# MCU_CAN.net
KiCad netlist of a schematic drawn in Altium Designer
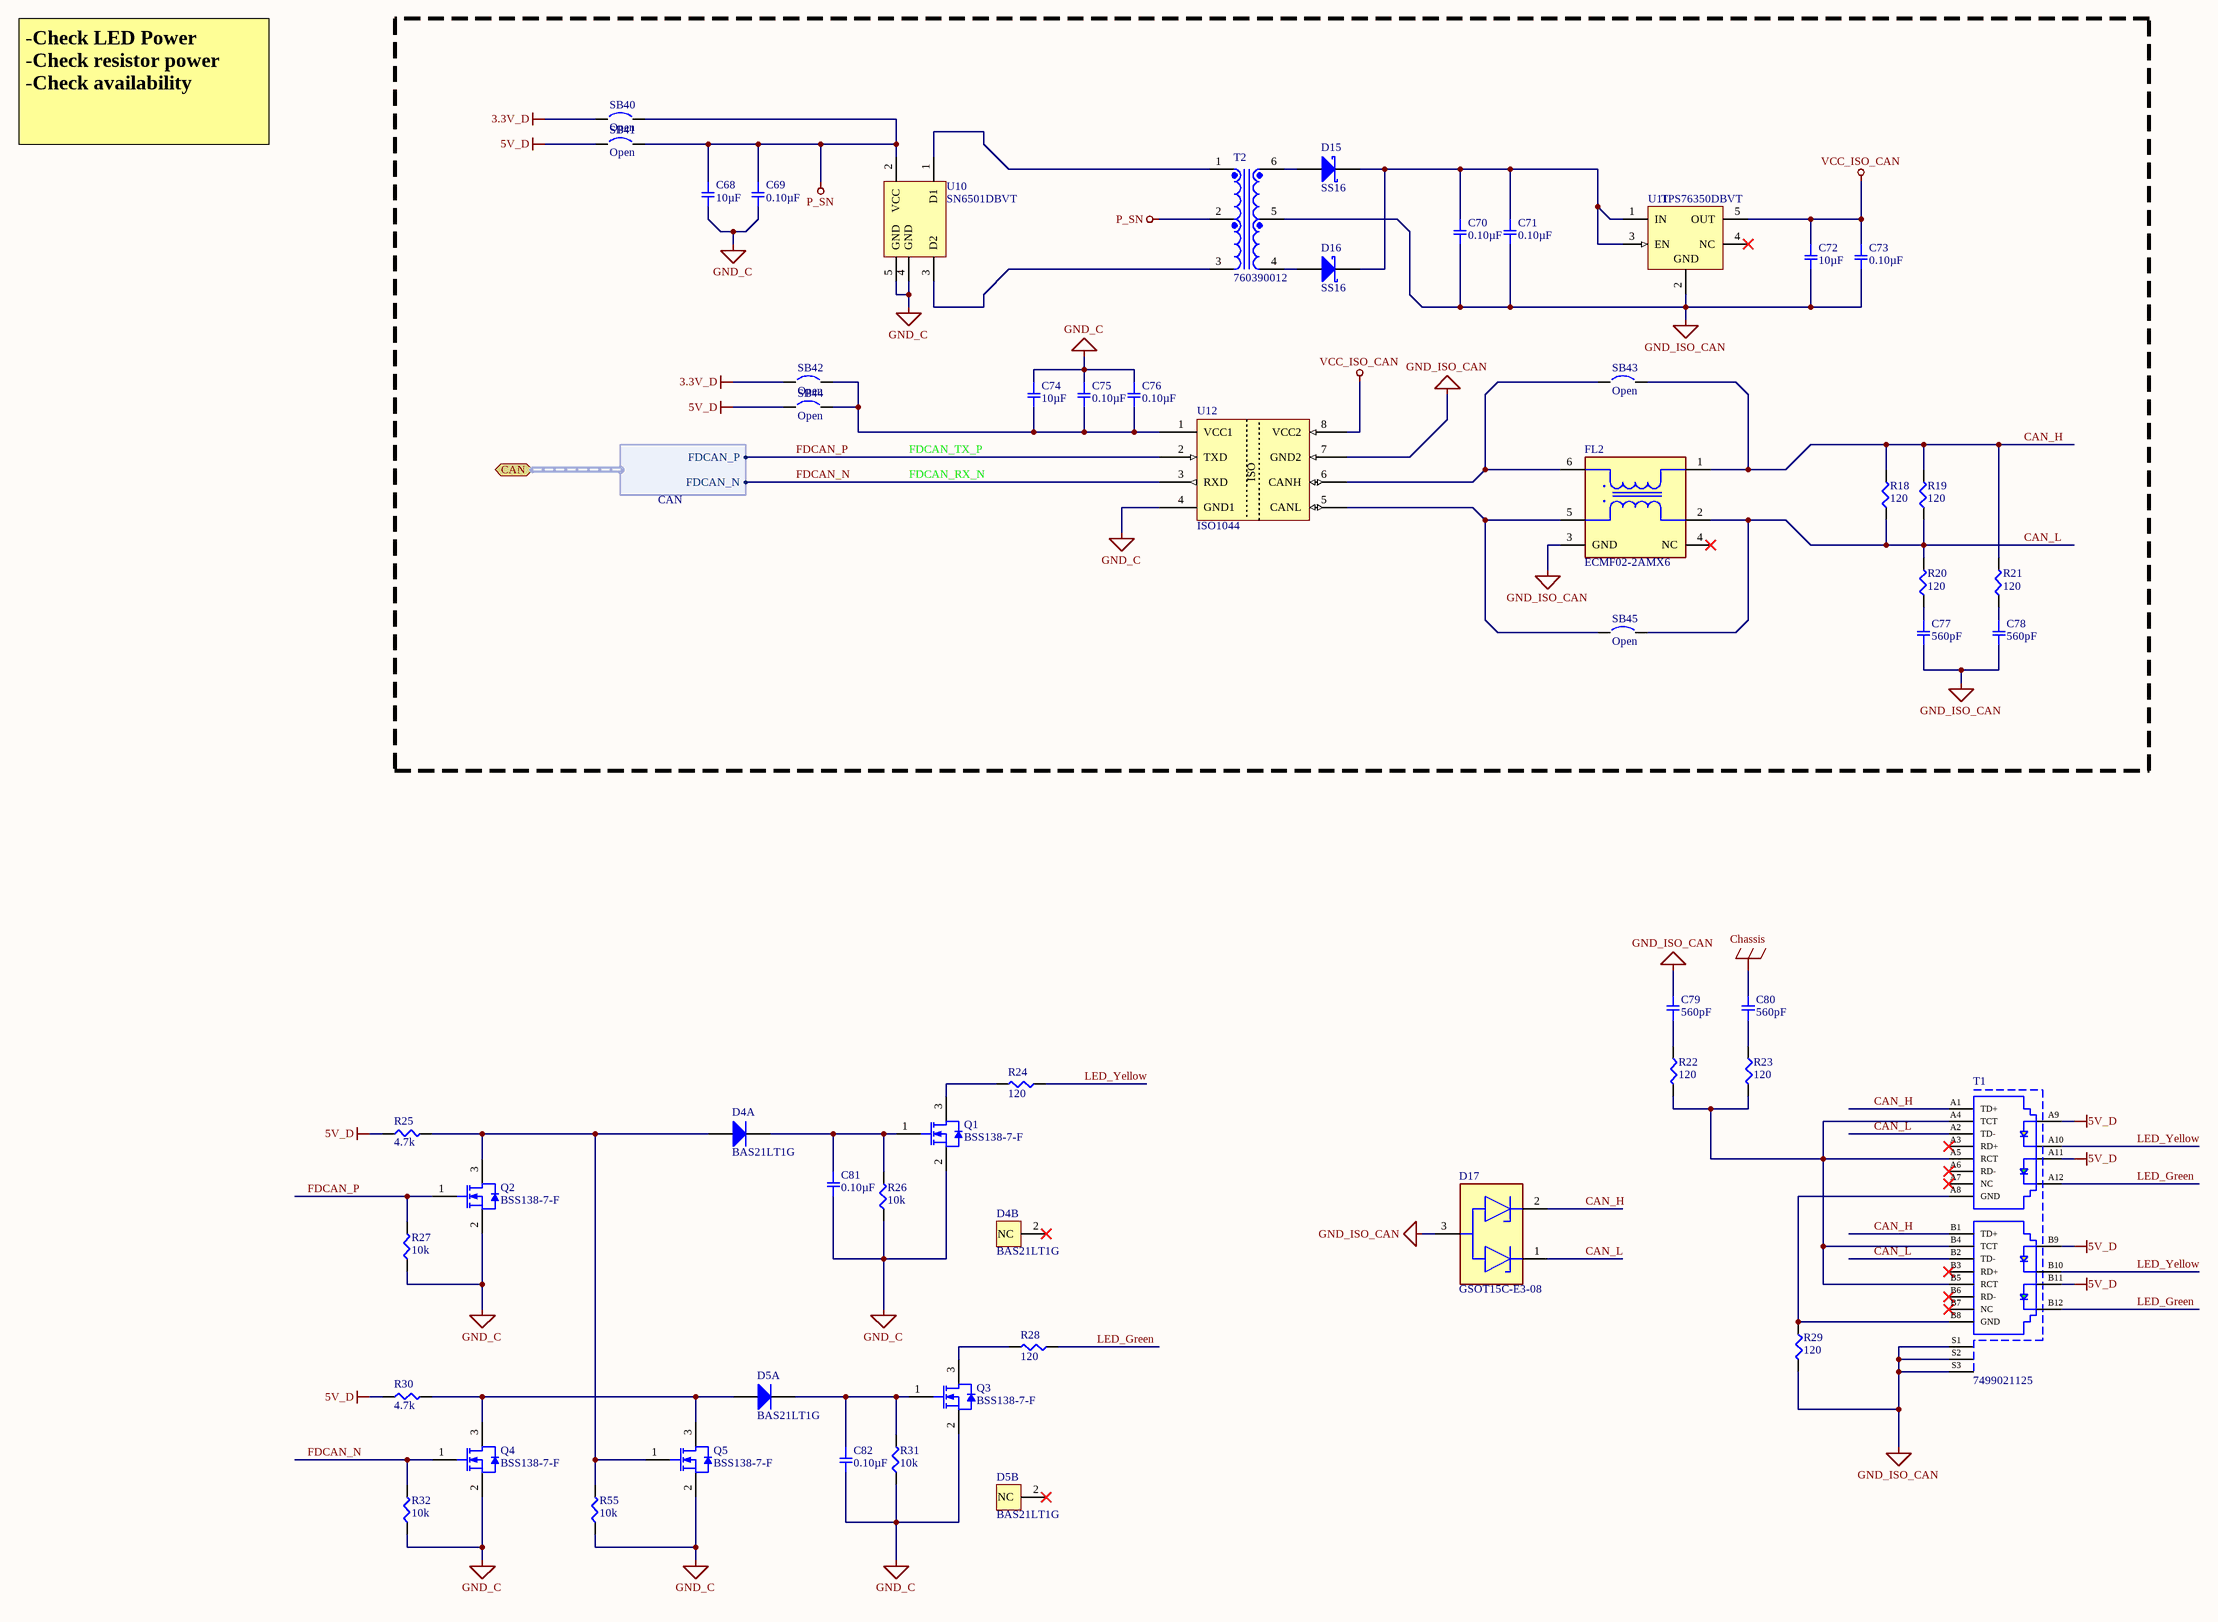
[diagram p0: MCU_CAN.SchDoc]

(export (version "E")
  (design (tool "Eeschema 10.0.6"))
  (components
    (comp (ref "C68")
      (value "10µF")
      (footprint "SMD-0805C")
      (description "CAP CER 10UF 10V X7R 0805")
      (fields
        (field (name "DIGI-KEY PART NUMBER") "490-10674-1-ND")
        (field (name "PART NUMBER") "GCM21BR71A106KE22L")
      )
      (libsource (lib "capacitor_murata_0805") (part "GCM21BR71A106KE22L"))
    )
    (comp (ref "C69")
      (value "0.10µF")
      (footprint "SMD-0805C")
      (description "CAP CER 0.1UF 100V X7R 0805")
      (fields
        (field (name "DIGI-KEY PART NUMBER") "490-5825-1-ND")
        (field (name "PART NUMBER") "GCJ21BR72A104KA01L")
      )
      (libsource (lib "capacitor_murata_0805") (part "GCJ21BR72A104KA01L"))
    )
    (comp (ref "C70")
      (value "0.10µF")
      (footprint "SMD-0805C")
      (description "CAP CER 0.1UF 100V X7R 0805")
      (fields
        (field (name "DIGI-KEY PART NUMBER") "490-5825-1-ND")
        (field (name "PART NUMBER") "GCJ21BR72A104KA01L")
      )
      (libsource (lib "capacitor_murata_0805") (part "GCJ21BR72A104KA01L"))
    )
    (comp (ref "C71")
      (value "0.10µF")
      (footprint "SMD-0805C")
      (description "CAP CER 0.1UF 100V X7R 0805")
      (fields
        (field (name "DIGI-KEY PART NUMBER") "490-5825-1-ND")
        (field (name "PART NUMBER") "GCJ21BR72A104KA01L")
      )
      (libsource (lib "capacitor_murata_0805") (part "GCJ21BR72A104KA01L"))
    )
    (comp (ref "C72")
      (value "10µF")
      (footprint "SMD-0805C")
      (description "CAP CER 10UF 10V X7R 0805")
      (fields
        (field (name "DIGI-KEY PART NUMBER") "490-10674-1-ND")
        (field (name "PART NUMBER") "GCM21BR71A106KE22L")
      )
      (libsource (lib "capacitor_murata_0805") (part "GCM21BR71A106KE22L"))
    )
    (comp (ref "C73")
      (value "0.10µF")
      (footprint "SMD-0805C")
      (description "CAP CER 0.1UF 100V X7R 0805")
      (fields
        (field (name "DIGI-KEY PART NUMBER") "490-5825-1-ND")
        (field (name "PART NUMBER") "GCJ21BR72A104KA01L")
      )
      (libsource (lib "capacitor_murata_0805") (part "GCJ21BR72A104KA01L"))
    )
    (comp (ref "C74")
      (value "10µF")
      (footprint "SMD-0805C")
      (description "CAP CER 10UF 10V X7R 0805")
      (fields
        (field (name "DIGI-KEY PART NUMBER") "490-10674-1-ND")
        (field (name "PART NUMBER") "GCM21BR71A106KE22L")
      )
      (libsource (lib "capacitor_murata_0805") (part "GCM21BR71A106KE22L"))
    )
    (comp (ref "C75")
      (value "0.10µF")
      (footprint "SMD-0805C")
      (description "CAP CER 0.1UF 100V X7R 0805")
      (fields
        (field (name "DIGI-KEY PART NUMBER") "490-5825-1-ND")
        (field (name "PART NUMBER") "GCJ21BR72A104KA01L")
      )
      (libsource (lib "capacitor_murata_0805") (part "GCJ21BR72A104KA01L"))
    )
    (comp (ref "C76")
      (value "0.10µF")
      (footprint "SMD-0805C")
      (description "CAP CER 0.1UF 100V X7R 0805")
      (fields
        (field (name "DIGI-KEY PART NUMBER") "490-5825-1-ND")
        (field (name "PART NUMBER") "GCJ21BR72A104KA01L")
      )
      (libsource (lib "capacitor_murata_0805") (part "GCJ21BR72A104KA01L"))
    )
    (comp (ref "C77")
      (value "560pF")
      (footprint "SMD-0805C")
      (description "CAP CER 560PF 50V X7R 0805")
      (fields
        (field (name "DIGI-KEY PART NUMBER") "490-11575-1-ND")
        (field (name "PART NUMBER") "GRM216R71H561KA01D")
      )
      (libsource (lib "capacitor_murata_0805") (part "GRM216R71H561KA01D"))
    )
    (comp (ref "C78")
      (value "560pF")
      (footprint "SMD-0805C")
      (description "CAP CER 560PF 50V X7R 0805")
      (fields
        (field (name "DIGI-KEY PART NUMBER") "490-11575-1-ND")
        (field (name "PART NUMBER") "GRM216R71H561KA01D")
      )
      (libsource (lib "capacitor_murata_0805") (part "GRM216R71H561KA01D"))
    )
    (comp (ref "C79")
      (value "560pF")
      (footprint "SMD-0805C")
      (description "CAP CER 560PF 50V X7R 0805")
      (fields
        (field (name "DIGI-KEY PART NUMBER") "490-11575-1-ND")
        (field (name "PART NUMBER") "GRM216R71H561KA01D")
      )
      (libsource (lib "capacitor_murata_0805") (part "GRM216R71H561KA01D"))
    )
    (comp (ref "C80")
      (value "560pF")
      (footprint "SMD-0805C")
      (description "CAP CER 560PF 50V X7R 0805")
      (fields
        (field (name "DIGI-KEY PART NUMBER") "490-11575-1-ND")
        (field (name "PART NUMBER") "GRM216R71H561KA01D")
      )
      (libsource (lib "capacitor_murata_0805") (part "GRM216R71H561KA01D"))
    )
    (comp (ref "C81")
      (value "0.10µF")
      (footprint "SMD-0805C")
      (description "CAP CER 0.1UF 100V X7R 0805")
      (fields
        (field (name "DIGI-KEY PART NUMBER") "490-5825-1-ND")
        (field (name "PART NUMBER") "GCJ21BR72A104KA01L")
      )
      (libsource (lib "capacitor_murata_0805") (part "GCJ21BR72A104KA01L"))
    )
    (comp (ref "C82")
      (value "0.10µF")
      (footprint "SMD-0805C")
      (description "CAP CER 0.1UF 100V X7R 0805")
      (fields
        (field (name "DIGI-KEY PART NUMBER") "490-5825-1-ND")
        (field (name "PART NUMBER") "GCJ21BR72A104KA01L")
      )
      (libsource (lib "capacitor_murata_0805") (part "GCJ21BR72A104KA01L"))
    )
    (comp (ref "D4")
      (value "BAS21LT1G")
      (footprint "ONSC-SOT-23-3-318-08_V")
      (description "High Voltage Switching Diode, 250 V, 3-Pin SOT-23 (318-08), Pb-Free, Tape and Reel")
      (fields (field (name "MANUFACTURER") "ON Semiconductor"))
      (libsource (lib "Altium Content Vault") (part "D-ANK-3"))
    )
    (comp (ref "D5")
      (value "BAS21LT1G")
      (footprint "ONSC-SOT-23-3-318-08_V")
      (description "High Voltage Switching Diode, 250 V, 3-Pin SOT-23 (318-08), Pb-Free, Tape and Reel")
      (fields (field (name "MANUFACTURER") "ON Semiconductor"))
      (libsource (lib "Altium Content Vault") (part "D-ANK-3"))
    )
    (comp (ref "D15")
      (value "SS16")
      (footprint "FAIR-SMA-2_B_V")
      (description "Schottky Rectifier, 700 mV, -65 to 125 degC, 2-Pin SMA, RoHS, Tape and Reel")
      (fields (field (name "MANUFACTURER") "FairchildSemiconductor"))
      (libsource (lib "Altium Content Vault") (part "DSKY-AK-2"))
    )
    (comp (ref "D16")
      (value "SS16")
      (footprint "FAIR-SMA-2_B_V")
      (description "Schottky Rectifier, 700 mV, -65 to 125 degC, 2-Pin SMA, RoHS, Tape and Reel")
      (fields (field (name "MANUFACTURER") "FairchildSemiconductor"))
      (libsource (lib "Altium Content Vault") (part "DSKY-AK-2"))
    )
    (comp (ref "D17")
      (value "GSOT15C-E3-08")
      (footprint "FP-6_541-5014_01-4-MFG")
      (description "TVS DIODE 15V 28.8V SOT23-3")
      (fields
        (field (name "MANUFACTURER") "Vishay")
        (field (name "OCTOPART") "https://octopart.com/gsot15c-e3-08-vishay-46467627")
      )
      (libsource (lib "Altium Content Vault") (part "6507c46d0de7a0efe814642e70f00b3"))
    )
    (comp (ref "FL2")
      (value "ECMF02-2AMX6")
      (footprint "FP-QFN-6L-MFG")
      (description "CMC 200MA 2LN SMD ESD")
      (fields
        (field (name "MANUFACTURER") "STMicroelectronics")
        (field (name "OCTOPART") "https://octopart.com/ecmf02-2amx6-stmicroelectronics-44353078")
      )
      (libsource (lib "Altium Content Vault") (part "8feffc7f24acfb857157da90e949b57"))
    )
    (comp (ref "Q1")
      (value "BSS138-7-F")
      (footprint "DIOD-SOT23-3_V")
      (description "N-Channel Enhancement Mode Mosfet, 50 V, 0.2 A, -55 to 150 degC, 3-Pin SOT23, RoHS, Tape and Reel")
      (fields (field (name "MANUFACTURER") "Diodes Inc"))
      (libsource (lib "Altium Content Vault") (part "NEMOS-GSD-3"))
    )
    (comp (ref "Q2")
      (value "BSS138-7-F")
      (footprint "DIOD-SOT23-3_V")
      (description "N-Channel Enhancement Mode Mosfet, 50 V, 0.2 A, -55 to 150 degC, 3-Pin SOT23, RoHS, Tape and Reel")
      (fields (field (name "MANUFACTURER") "Diodes Inc"))
      (libsource (lib "Altium Content Vault") (part "NEMOS-GSD-3"))
    )
    (comp (ref "Q3")
      (value "BSS138-7-F")
      (footprint "DIOD-SOT23-3_V")
      (description "N-Channel Enhancement Mode Mosfet, 50 V, 0.2 A, -55 to 150 degC, 3-Pin SOT23, RoHS, Tape and Reel")
      (fields (field (name "MANUFACTURER") "Diodes Inc"))
      (libsource (lib "Altium Content Vault") (part "NEMOS-GSD-3"))
    )
    (comp (ref "Q4")
      (value "BSS138-7-F")
      (footprint "DIOD-SOT23-3_V")
      (description "N-Channel Enhancement Mode Mosfet, 50 V, 0.2 A, -55 to 150 degC, 3-Pin SOT23, RoHS, Tape and Reel")
      (fields (field (name "MANUFACTURER") "Diodes Inc"))
      (libsource (lib "Altium Content Vault") (part "NEMOS-GSD-3"))
    )
    (comp (ref "Q5")
      (value "BSS138-7-F")
      (footprint "DIOD-SOT23-3_V")
      (description "N-Channel Enhancement Mode Mosfet, 50 V, 0.2 A, -55 to 150 degC, 3-Pin SOT23, RoHS, Tape and Reel")
      (fields (field (name "MANUFACTURER") "Diodes Inc"))
      (libsource (lib "Altium Content Vault") (part "NEMOS-GSD-3"))
    )
    (comp (ref "R18")
      (value "120")
      (footprint "SMD-0603-RES")
      (description "RES SMD 120 OHM 1% 1/10W 0603")
      (fields (field (name "PART NUMBER") "ERJ-3EKF1200V") (field (name "DIGI-KEY PART NUMBER") "P120HCT-ND"))
      (libsource (lib "Panasonic_ERJ_0603") (part "ERJ-3EKF1200V"))
    )
    (comp (ref "R19")
      (value "120")
      (footprint "SMD-0603-RES")
      (description "RES SMD 120 OHM 1% 1/10W 0603")
      (fields (field (name "PART NUMBER") "ERJ-3EKF1200V") (field (name "DIGI-KEY PART NUMBER") "P120HCT-ND"))
      (libsource (lib "Panasonic_ERJ_0603") (part "ERJ-3EKF1200V"))
    )
    (comp (ref "R20")
      (value "120")
      (footprint "SMD-0603-RES")
      (description "RES SMD 120 OHM 1% 1/10W 0603")
      (fields (field (name "PART NUMBER") "ERJ-3EKF1200V") (field (name "DIGI-KEY PART NUMBER") "P120HCT-ND"))
      (libsource (lib "Panasonic_ERJ_0603") (part "ERJ-3EKF1200V"))
    )
    (comp (ref "R21")
      (value "120")
      (footprint "SMD-0603-RES")
      (description "RES SMD 120 OHM 1% 1/10W 0603")
      (fields (field (name "PART NUMBER") "ERJ-3EKF1200V") (field (name "DIGI-KEY PART NUMBER") "P120HCT-ND"))
      (libsource (lib "Panasonic_ERJ_0603") (part "ERJ-3EKF1200V"))
    )
    (comp (ref "R22")
      (value "120")
      (footprint "SMD-0603-RES")
      (description "RES SMD 120 OHM 1% 1/10W 0603")
      (fields (field (name "PART NUMBER") "ERJ-3EKF1200V") (field (name "DIGI-KEY PART NUMBER") "P120HCT-ND"))
      (libsource (lib "Panasonic_ERJ_0603") (part "ERJ-3EKF1200V"))
    )
    (comp (ref "R23")
      (value "120")
      (footprint "SMD-0603-RES")
      (description "RES SMD 120 OHM 1% 1/10W 0603")
      (fields (field (name "PART NUMBER") "ERJ-3EKF1200V") (field (name "DIGI-KEY PART NUMBER") "P120HCT-ND"))
      (libsource (lib "Panasonic_ERJ_0603") (part "ERJ-3EKF1200V"))
    )
    (comp (ref "R24")
      (value "120")
      (footprint "SMD-0603-RES")
      (description "RES SMD 120 OHM 1% 1/10W 0603")
      (fields (field (name "PART NUMBER") "ERJ-3EKF1200V") (field (name "DIGI-KEY PART NUMBER") "P120HCT-ND"))
      (libsource (lib "Panasonic_ERJ_0603") (part "ERJ-3EKF1200V"))
    )
    (comp (ref "R25")
      (value "4.7k")
      (footprint "SMD-0603-RES")
      (description "RES SMD 4.7K OHM 1% 1/10W 0603")
      (fields
        (field (name "PART NUMBER") "ERJ-3EKF4701V")
        (field (name "DIGI-KEY PART NUMBER") "P4.70KHCT-ND")
      )
      (libsource (lib "Panasonic_ERJ_0603") (part "ERJ-3EKF4701V"))
    )
    (comp (ref "R26")
      (value "10k")
      (footprint "SMD-0603-RES")
      (description "RES SMD 10K OHM 1% 1/10W 0603")
      (fields
        (field (name "PART NUMBER") "ERJ-3EKF1002V")
        (field (name "DIGI-KEY PART NUMBER") "P10.0KHCT-ND")
      )
      (libsource (lib "Panasonic_ERJ_0603") (part "ERJ-3EKF1002V"))
    )
    (comp (ref "R27")
      (value "10k")
      (footprint "SMD-0603-RES")
      (description "RES SMD 10K OHM 1% 1/10W 0603")
      (fields
        (field (name "PART NUMBER") "ERJ-3EKF1002V")
        (field (name "DIGI-KEY PART NUMBER") "P10.0KHCT-ND")
      )
      (libsource (lib "Panasonic_ERJ_0603") (part "ERJ-3EKF1002V"))
    )
    (comp (ref "R28")
      (value "120")
      (footprint "SMD-0603-RES")
      (description "RES SMD 120 OHM 1% 1/10W 0603")
      (fields (field (name "PART NUMBER") "ERJ-3EKF1200V") (field (name "DIGI-KEY PART NUMBER") "P120HCT-ND"))
      (libsource (lib "Panasonic_ERJ_0603") (part "ERJ-3EKF1200V"))
    )
    (comp (ref "R29")
      (value "120")
      (footprint "SMD-0603-RES")
      (description "RES SMD 120 OHM 1% 1/10W 0603")
      (fields (field (name "PART NUMBER") "ERJ-3EKF1200V") (field (name "DIGI-KEY PART NUMBER") "P120HCT-ND"))
      (libsource (lib "Panasonic_ERJ_0603") (part "ERJ-3EKF1200V"))
    )
    (comp (ref "R30")
      (value "4.7k")
      (footprint "SMD-0603-RES")
      (description "RES SMD 4.7K OHM 1% 1/10W 0603")
      (fields
        (field (name "PART NUMBER") "ERJ-3EKF4701V")
        (field (name "DIGI-KEY PART NUMBER") "P4.70KHCT-ND")
      )
      (libsource (lib "Panasonic_ERJ_0603") (part "ERJ-3EKF4701V"))
    )
    (comp (ref "R31")
      (value "10k")
      (footprint "SMD-0603-RES")
      (description "RES SMD 10K OHM 1% 1/10W 0603")
      (fields
        (field (name "PART NUMBER") "ERJ-3EKF1002V")
        (field (name "DIGI-KEY PART NUMBER") "P10.0KHCT-ND")
      )
      (libsource (lib "Panasonic_ERJ_0603") (part "ERJ-3EKF1002V"))
    )
    (comp (ref "R32")
      (value "10k")
      (footprint "SMD-0603-RES")
      (description "RES SMD 10K OHM 1% 1/10W 0603")
      (fields
        (field (name "PART NUMBER") "ERJ-3EKF1002V")
        (field (name "DIGI-KEY PART NUMBER") "P10.0KHCT-ND")
      )
      (libsource (lib "Panasonic_ERJ_0603") (part "ERJ-3EKF1002V"))
    )
    (comp (ref "R55")
      (value "10k")
      (footprint "SMD-0603-RES")
      (description "RES SMD 10K OHM 1% 1/10W 0603")
      (fields
        (field (name "PART NUMBER") "ERJ-3EKF1002V")
        (field (name "DIGI-KEY PART NUMBER") "P10.0KHCT-ND")
      )
      (libsource (lib "Panasonic_ERJ_0603") (part "ERJ-3EKF1002V"))
    )
    (comp (ref "SB40")
      (value "Open")
      (footprint "SB_0603")
      (description "Circuit Breaker")
      (fields (field (name "PUBLISHER") "Altium Limited"))
      (libsource (lib "Edge_Card_Ucc28951") (part "Solder Bridge"))
    )
    (comp (ref "SB41")
      (value "Open")
      (footprint "SB_0603")
      (description "Circuit Breaker")
      (fields (field (name "PUBLISHER") "Altium Limited"))
      (libsource (lib "Edge_Card_Ucc28951") (part "Solder Bridge"))
    )
    (comp (ref "SB42")
      (value "Open")
      (footprint "SB_0603")
      (description "Circuit Breaker")
      (fields (field (name "PUBLISHER") "Altium Limited"))
      (libsource (lib "Edge_Card_Ucc28951") (part "Solder Bridge"))
    )
    (comp (ref "SB43")
      (value "Open")
      (footprint "SB_0603")
      (description "Circuit Breaker")
      (fields (field (name "PUBLISHER") "Altium Limited"))
      (libsource (lib "Edge_Card_Ucc28951") (part "Solder Bridge"))
    )
    (comp (ref "SB44")
      (value "Open")
      (footprint "SB_0603")
      (description "Circuit Breaker")
      (fields (field (name "PUBLISHER") "Altium Limited"))
      (libsource (lib "Edge_Card_Ucc28951") (part "Solder Bridge"))
    )
    (comp (ref "SB45")
      (value "Open")
      (footprint "SB_0603")
      (description "Circuit Breaker")
      (fields (field (name "PUBLISHER") "Altium Limited"))
      (libsource (lib "Edge_Card_Ucc28951") (part "Solder Bridge"))
    )
    (comp (ref "T1")
      (value "7499021125")
      (footprint "7499021125")
      (description "WE-RJ45 LAN Transformer, THT, 10/100 Base-T, Port 1x2, Tab Down")
      (fields (field (name "PUBLISHER") "Wurth Elektronik"))
      (libsource (lib "7499021125_Altium_WE-RJ45LAN_rev20a") (part "7499021125"))
    )
    (comp (ref "T2")
      (value "760390012")
      (footprint "WE-760390012-6_V")
      (description "Transformer, 150 mA, -40 to 125 degC, 6-Pin SMD, RoHS, Tape and Reel")
      (fields (field (name "MANUFACTURER") "Wuerth Elektronik"))
      (libsource (lib "Edge_Card_Ucc28951") (part "760039112"))
    )
    (comp (ref "U10")
      (value "SN6501DBVT")
      (footprint "SOT95P278X110-5N")
      (fields (field (name "MANUFACTURER") "TexasInstruments"))
      (libsource (lib "Edge_Card_Ucc28951") (part "SN6501"))
    )
    (comp (ref "U11")
      (value "TPS76350DBVT")
      (footprint "DBV0005A_M")
      (fields (field (name "MANUFACTURER") "Texas Instruments"))
      (libsource (lib "Altium Content Vault") (part "TI-TXX7XXXX-5"))
    )
    (comp (ref "U12")
      (value "ISO1044")
      (footprint "SOIC127P570X175_HS-9N - No Thermal")
      (description "Isolated FD CAN Transreciever")
      (libsource (lib "Edge_Card_Ucc28951") (part "ISO1044"))
    )
  )
  (nets
    (net (code "2") (name "/CAN_H") (class "Default")
      (node (ref "D17") (pin "2") (pinfunction "2_CATHODE_2") (pintype "passive"))
      (node (ref "FL2") (pin "1") (pinfunction "D+_1") (pintype "passive"))
      (node (ref "R18") (pin "2") (pinfunction "2_2") (pintype "passive"))
      (node (ref "R19") (pin "2") (pinfunction "2_2") (pintype "passive"))
      (node (ref "R21") (pin "2") (pinfunction "2_2") (pintype "passive"))
      (node (ref "SB43") (pin "2") (pinfunction "2_2") (pintype "passive"))
      (node (ref "T1") (pin "A1") (pinfunction "TD+_A1") (pintype "passive"))
      (node (ref "T1") (pin "B1") (pinfunction "TD+_B1") (pintype "passive"))
    )
    (net (code "3") (name "/CAN_L") (class "Default")
      (node (ref "D17") (pin "1") (pinfunction "1_CATHODE_1") (pintype "passive"))
      (node (ref "FL2") (pin "2") (pinfunction "D-_2") (pintype "passive"))
      (node (ref "R18") (pin "1") (pinfunction "1_1") (pintype "passive"))
      (node (ref "R19") (pin "1") (pinfunction "1_1") (pintype "passive"))
      (node (ref "R20") (pin "2") (pinfunction "2_2") (pintype "passive"))
      (node (ref "SB45") (pin "2") (pinfunction "2_2") (pintype "passive"))
      (node (ref "T1") (pin "A2") (pinfunction "TD-_A2") (pintype "passive"))
      (node (ref "T1") (pin "B2") (pinfunction "TD-_B2") (pintype "passive"))
    )
    (net (code "4") (name "/FDCAN_N") (class "Default")
      (node (ref "Q4") (pin "1") (pinfunction "G_1") (pintype "passive"))
      (node (ref "R32") (pin "2") (pinfunction "2_2") (pintype "passive"))
      (node (ref "U12") (pin "3") (pinfunction "RXD_3") (pintype "output"))
    )
    (net (code "5") (name "/FDCAN_P") (class "Default")
      (node (ref "Q2") (pin "1") (pinfunction "G_1") (pintype "passive"))
      (node (ref "R27") (pin "2") (pinfunction "2_2") (pintype "passive"))
      (node (ref "U12") (pin "2") (pinfunction "TXD_2") (pintype "input"))
    )
    (net (code "6") (name "/LED_Green") (class "Default")
      (node (ref "R28") (pin "1") (pinfunction "1_1") (pintype "passive"))
      (node (ref "T1") (pin "A12") (pinfunction "A12_A12") (pintype "passive"))
      (node (ref "T1") (pin "B12") (pinfunction "B12_B12") (pintype "passive"))
    )
    (net (code "7") (name "/LED_Yellow") (class "Default")
      (node (ref "R24") (pin "1") (pinfunction "1_1") (pintype "passive"))
      (node (ref "T1") (pin "A10") (pinfunction "A10_A10") (pintype "passive"))
      (node (ref "T1") (pin "B10") (pinfunction "B10_B10") (pintype "passive"))
    )
    (net (code "9") (name "3.3V_D") (class "Default")
      (node (ref "SB40") (pin "1") (pinfunction "1_1") (pintype "passive"))
      (node (ref "SB42") (pin "1") (pinfunction "1_1") (pintype "passive"))
    )
    (net (code "10") (name "5V_D") (class "Default")
      (node (ref "R25") (pin "1") (pinfunction "1_1") (pintype "passive"))
      (node (ref "R30") (pin "1") (pinfunction "1_1") (pintype "passive"))
      (node (ref "SB41") (pin "1") (pinfunction "1_1") (pintype "passive"))
      (node (ref "SB44") (pin "1") (pinfunction "1_1") (pintype "passive"))
      (node (ref "T1") (pin "A11") (pinfunction "A11_A11") (pintype "passive"))
      (node (ref "T1") (pin "A9") (pinfunction "A9_A9") (pintype "passive"))
      (node (ref "T1") (pin "B11") (pinfunction "B11_B11") (pintype "passive"))
      (node (ref "T1") (pin "B9") (pinfunction "B9_B9") (pintype "passive"))
    )
    (net (code "11") (name "Chassis") (class "Default")
      (node (ref "C80") (pin "2") (pinfunction "2_2") (pintype "passive"))
    )
    (net (code "12") (name "GND_C") (class "Default")
      (node (ref "C68") (pin "2") (pinfunction "2_2") (pintype "passive"))
      (node (ref "C69") (pin "2") (pinfunction "2_2") (pintype "passive"))
      (node (ref "C74") (pin "1") (pinfunction "1_1") (pintype "passive"))
      (node (ref "C75") (pin "1") (pinfunction "1_1") (pintype "passive"))
      (node (ref "C76") (pin "1") (pinfunction "1_1") (pintype "passive"))
      (node (ref "C81") (pin "2") (pinfunction "2_2") (pintype "passive"))
      (node (ref "C82") (pin "2") (pinfunction "2_2") (pintype "passive"))
      (node (ref "Q1") (pin "2") (pinfunction "S_2") (pintype "passive"))
      (node (ref "Q2") (pin "2") (pinfunction "S_2") (pintype "passive"))
      (node (ref "Q3") (pin "2") (pinfunction "S_2") (pintype "passive"))
      (node (ref "Q4") (pin "2") (pinfunction "S_2") (pintype "passive"))
      (node (ref "Q5") (pin "2") (pinfunction "S_2") (pintype "passive"))
      (node (ref "R26") (pin "1") (pinfunction "1_1") (pintype "passive"))
      (node (ref "R27") (pin "1") (pinfunction "1_1") (pintype "passive"))
      (node (ref "R31") (pin "1") (pinfunction "1_1") (pintype "passive"))
      (node (ref "R32") (pin "1") (pinfunction "1_1") (pintype "passive"))
      (node (ref "R55") (pin "1") (pinfunction "1_1") (pintype "passive"))
      (node (ref "U10") (pin "4") (pinfunction "GND_4") (pintype "power_in"))
      (node (ref "U10") (pin "5") (pinfunction "GND_5") (pintype "power_in"))
      (node (ref "U12") (pin "4") (pinfunction "GND1_4") (pintype "power_in"))
    )
    (net (code "13") (name "GND_ISO_CAN") (class "Default")
      (node (ref "C70") (pin "2") (pinfunction "2_2") (pintype "passive"))
      (node (ref "C71") (pin "2") (pinfunction "2_2") (pintype "passive"))
      (node (ref "C72") (pin "2") (pinfunction "2_2") (pintype "passive"))
      (node (ref "C73") (pin "2") (pinfunction "2_2") (pintype "passive"))
      (node (ref "C77") (pin "2") (pinfunction "2_2") (pintype "passive"))
      (node (ref "C78") (pin "2") (pinfunction "2_2") (pintype "passive"))
      (node (ref "C79") (pin "2") (pinfunction "2_2") (pintype "passive"))
      (node (ref "D17") (pin "3") (pinfunction "COMMON_ANODE_3") (pintype "passive"))
      (node (ref "FL2") (pin "3") (pinfunction "GND_3") (pintype "power_in"))
      (node (ref "R29") (pin "2") (pinfunction "2_2") (pintype "passive"))
      (node (ref "T1") (pin "S1") (pinfunction "Shield_S1") (pintype "passive"))
      (node (ref "T1") (pin "S2") (pinfunction "Shield_S2") (pintype "passive"))
      (node (ref "T1") (pin "S3") (pinfunction "Shield_S3") (pintype "passive"))
      (node (ref "T2") (pin "5") (pinfunction "5_5") (pintype "passive"))
      (node (ref "U11") (pin "2") (pinfunction "GND_2") (pintype "power_in"))
      (node (ref "U12") (pin "7") (pinfunction "GND2_7") (pintype "input"))
    )
    (net (code "14") (name "Net-(C77-Pad1)") (class "Default")
      (node (ref "C77") (pin "1") (pinfunction "1_1") (pintype "passive"))
      (node (ref "R20") (pin "1") (pinfunction "1_1") (pintype "passive"))
    )
    (net (code "15") (name "Net-(C78-Pad1)") (class "Default")
      (node (ref "C78") (pin "1") (pinfunction "1_1") (pintype "passive"))
      (node (ref "R21") (pin "1") (pinfunction "1_1") (pintype "passive"))
    )
    (net (code "16") (name "Net-(C79-Pad1)") (class "Default")
      (node (ref "C79") (pin "1") (pinfunction "1_1") (pintype "passive"))
      (node (ref "R22") (pin "1") (pinfunction "1_1") (pintype "passive"))
    )
    (net (code "17") (name "Net-(C80-Pad1)") (class "Default")
      (node (ref "C80") (pin "1") (pinfunction "1_1") (pintype "passive"))
      (node (ref "R23") (pin "1") (pinfunction "1_1") (pintype "passive"))
    )
    (net (code "18") (name "Net-(D4A-A)") (class "Default")
      (node (ref "D4") (pin "1") (pinfunction "A_1") (pintype "passive"))
      (node (ref "Q2") (pin "3") (pinfunction "D_3") (pintype "passive"))
      (node (ref "Q5") (pin "1") (pinfunction "G_1") (pintype "passive"))
      (node (ref "R25") (pin "2") (pinfunction "2_2") (pintype "passive"))
      (node (ref "R55") (pin "2") (pinfunction "2_2") (pintype "passive"))
    )
    (net (code "19") (name "Net-(D4A-K)") (class "Default")
      (node (ref "C81") (pin "1") (pinfunction "1_1") (pintype "passive"))
      (node (ref "D4") (pin "3") (pinfunction "K_3") (pintype "passive"))
      (node (ref "Q1") (pin "1") (pinfunction "G_1") (pintype "passive"))
      (node (ref "R26") (pin "2") (pinfunction "2_2") (pintype "passive"))
    )
    (net (code "20") (name "Net-(D5A-A)") (class "Default")
      (node (ref "D5") (pin "1") (pinfunction "A_1") (pintype "passive"))
      (node (ref "Q4") (pin "3") (pinfunction "D_3") (pintype "passive"))
      (node (ref "Q5") (pin "3") (pinfunction "D_3") (pintype "passive"))
      (node (ref "R30") (pin "2") (pinfunction "2_2") (pintype "passive"))
    )
    (net (code "21") (name "Net-(D5A-K)") (class "Default")
      (node (ref "C82") (pin "1") (pinfunction "1_1") (pintype "passive"))
      (node (ref "D5") (pin "3") (pinfunction "K_3") (pintype "passive"))
      (node (ref "Q3") (pin "1") (pinfunction "G_1") (pintype "passive"))
      (node (ref "R31") (pin "2") (pinfunction "2_2") (pintype "passive"))
    )
    (net (code "22") (name "Net-(D15-A)") (class "Default")
      (node (ref "D15") (pin "1") (pinfunction "A_1") (pintype "passive"))
      (node (ref "T2") (pin "6") (pinfunction "6_6") (pintype "passive"))
    )
    (net (code "23") (name "Net-(D15-K)") (class "Default")
      (node (ref "C70") (pin "1") (pinfunction "1_1") (pintype "passive"))
      (node (ref "C71") (pin "1") (pinfunction "1_1") (pintype "passive"))
      (node (ref "D15") (pin "2") (pinfunction "K_2") (pintype "passive"))
      (node (ref "D16") (pin "2") (pinfunction "K_2") (pintype "passive"))
      (node (ref "U11") (pin "1") (pinfunction "IN_1") (pintype "power_in"))
      (node (ref "U11") (pin "3") (pinfunction "EN_3") (pintype "input"))
    )
    (net (code "24") (name "Net-(D16-A)") (class "Default")
      (node (ref "D16") (pin "1") (pinfunction "A_1") (pintype "passive"))
      (node (ref "T2") (pin "4") (pinfunction "4_4") (pintype "passive"))
    )
    (net (code "25") (name "Net-(Q1-D)") (class "Default")
      (node (ref "Q1") (pin "3") (pinfunction "D_3") (pintype "passive"))
      (node (ref "R24") (pin "2") (pinfunction "2_2") (pintype "passive"))
    )
    (net (code "26") (name "Net-(Q3-D)") (class "Default")
      (node (ref "Q3") (pin "3") (pinfunction "D_3") (pintype "passive"))
      (node (ref "R28") (pin "2") (pinfunction "2_2") (pintype "passive"))
    )
    (net (code "27") (name "Net-(R22-Pad2)") (class "Default")
      (node (ref "R22") (pin "2") (pinfunction "2_2") (pintype "passive"))
      (node (ref "R23") (pin "2") (pinfunction "2_2") (pintype "passive"))
      (node (ref "T1") (pin "A4") (pinfunction "TCT_A4") (pintype "passive"))
      (node (ref "T1") (pin "A5") (pinfunction "RCT_A5") (pintype "passive"))
      (node (ref "T1") (pin "B4") (pinfunction "TCT_B4") (pintype "passive"))
      (node (ref "T1") (pin "B5") (pinfunction "RCT_B5") (pintype "passive"))
    )
    (net (code "28") (name "Net-(R29-Pad1)") (class "Default")
      (node (ref "R29") (pin "1") (pinfunction "1_1") (pintype "passive"))
      (node (ref "T1") (pin "A8") (pinfunction "GND_A8") (pintype "passive"))
      (node (ref "T1") (pin "B8") (pinfunction "GND_B8") (pintype "passive"))
    )
    (net (code "29") (name "Net-(U10-D1)") (class "Default")
      (node (ref "T2") (pin "1") (pinfunction "1_1") (pintype "passive"))
      (node (ref "U10") (pin "1") (pinfunction "D1_1") (pintype "open_collector"))
    )
    (net (code "30") (name "Net-(U10-D2)") (class "Default")
      (node (ref "T2") (pin "3") (pinfunction "3_3") (pintype "passive"))
      (node (ref "U10") (pin "3") (pinfunction "D2_3") (pintype "open_collector"))
    )
    (net (code "31") (name "Net-(U12-CANH)") (class "Default")
      (node (ref "FL2") (pin "6") (pinfunction "D+_6") (pintype "passive"))
      (node (ref "SB43") (pin "1") (pinfunction "1_1") (pintype "passive"))
      (node (ref "U12") (pin "6") (pinfunction "CANH_6") (pintype "bidirectional"))
    )
    (net (code "32") (name "Net-(U12-CANL)") (class "Default")
      (node (ref "FL2") (pin "5") (pinfunction "D-_5") (pintype "passive"))
      (node (ref "SB45") (pin "1") (pinfunction "1_1") (pintype "passive"))
      (node (ref "U12") (pin "5") (pinfunction "CANL_5") (pintype "bidirectional"))
    )
    (net (code "33") (name "Net-(U12-VCC1)") (class "Default")
      (node (ref "C74") (pin "2") (pinfunction "2_2") (pintype "passive"))
      (node (ref "C75") (pin "2") (pinfunction "2_2") (pintype "passive"))
      (node (ref "C76") (pin "2") (pinfunction "2_2") (pintype "passive"))
      (node (ref "SB42") (pin "2") (pinfunction "2_2") (pintype "passive"))
      (node (ref "SB44") (pin "2") (pinfunction "2_2") (pintype "passive"))
      (node (ref "U12") (pin "1") (pinfunction "VCC1_1") (pintype "power_in"))
    )
    (net (code "34") (name "P_SN") (class "Default")
      (node (ref "C68") (pin "1") (pinfunction "1_1") (pintype "passive"))
      (node (ref "C69") (pin "1") (pinfunction "1_1") (pintype "passive"))
      (node (ref "SB40") (pin "2") (pinfunction "2_2") (pintype "passive"))
      (node (ref "SB41") (pin "2") (pinfunction "2_2") (pintype "passive"))
      (node (ref "T2") (pin "2") (pinfunction "2_2") (pintype "passive"))
      (node (ref "U10") (pin "2") (pinfunction "VCC_2") (pintype "power_in"))
    )
    (net (code "35") (name "VCC_ISO_CAN") (class "Default")
      (node (ref "C72") (pin "1") (pinfunction "1_1") (pintype "passive"))
      (node (ref "C73") (pin "1") (pinfunction "1_1") (pintype "passive"))
      (node (ref "U11") (pin "5") (pinfunction "OUT_5") (pintype "power_in"))
      (node (ref "U12") (pin "8") (pinfunction "VCC2_8") (pintype "input"))
    )
    (net (code "36") (name "unconnected-(D4B-NC-Pad2)") (class "Default")
      (node (ref "D4") (pin "2") (pinfunction "NC_2") (pintype "passive+no_connect"))
    )
    (net (code "37") (name "unconnected-(D5B-NC-Pad2)") (class "Default")
      (node (ref "D5") (pin "2") (pinfunction "NC_2") (pintype "passive+no_connect"))
    )
    (net (code "38") (name "unconnected-(FL2-NC-Pad4)") (class "Default")
      (node (ref "FL2") (pin "4") (pinfunction "NC_4") (pintype "passive+no_connect"))
    )
    (net (code "39") (name "unconnected-(T1-NC-PadA7)") (class "Default")
      (node (ref "T1") (pin "A7") (pinfunction "NC_A7") (pintype "passive+no_connect"))
    )
    (net (code "40") (name "unconnected-(T1-NC-PadB7)") (class "Default")
      (node (ref "T1") (pin "B7") (pinfunction "NC_B7") (pintype "passive+no_connect"))
    )
    (net (code "41") (name "unconnected-(T1-RD+-PadA3)") (class "Default")
      (node (ref "T1") (pin "A3") (pinfunction "RD+_A3") (pintype "passive+no_connect"))
    )
    (net (code "42") (name "unconnected-(T1-RD+-PadB3)") (class "Default")
      (node (ref "T1") (pin "B3") (pinfunction "RD+_B3") (pintype "passive+no_connect"))
    )
    (net (code "43") (name "unconnected-(T1-RD--PadA6)") (class "Default")
      (node (ref "T1") (pin "A6") (pinfunction "RD-_A6") (pintype "passive+no_connect"))
    )
    (net (code "44") (name "unconnected-(T1-RD--PadB6)") (class "Default")
      (node (ref "T1") (pin "B6") (pinfunction "RD-_B6") (pintype "passive+no_connect"))
    )
    (net (code "45") (name "unconnected-(U11-NC-Pad4)") (class "Default")
      (node (ref "U11") (pin "4") (pinfunction "NC_4") (pintype "passive+no_connect"))
    )
  )
)
